# PCF8574.net
KiCad netlist of a schematic drawn in EAGLE
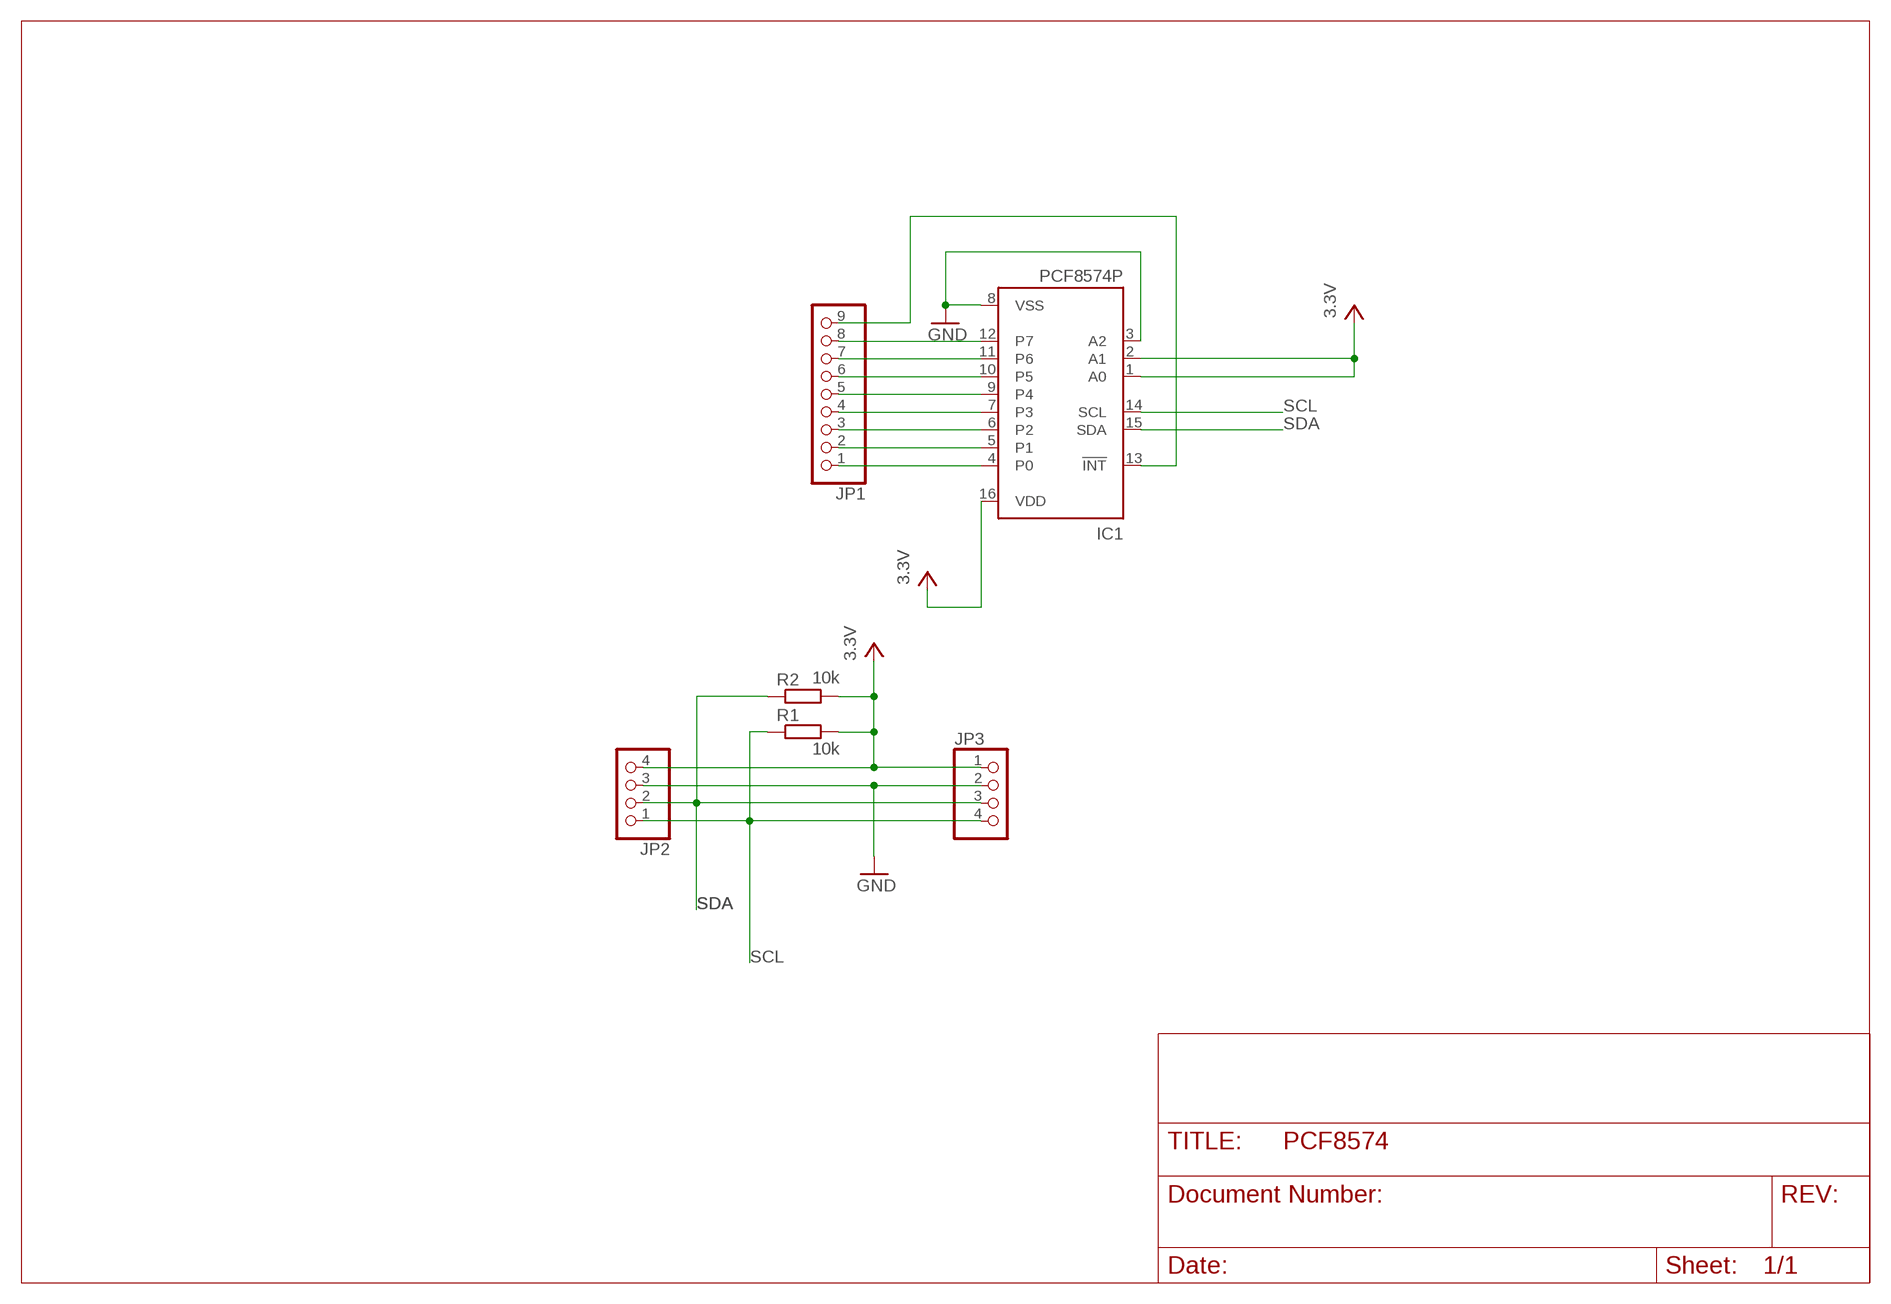
[diagram p0: schematic, sheet 1]

(export (version "E")
  (design (tool "Eeschema 10.0.6"))
  (components
    (comp (ref "IC1")
      (value "PCF8574P")
      (footprint "eagle-import:DIL16")
      (fields (field (name "MPN") "PCF8574PN"))
      (libsource (lib "eagle-import") (part "PCF8574P"))
    )
    (comp (ref "JP1")
      (value "PINHD-1X9")
      (footprint "eagle-import:1X09")
      (libsource (lib "eagle-import") (part "PINHD-1X9"))
    )
    (comp (ref "JP2")
      (value "PINHD-1X4/90")
      (footprint "eagle-import:1X04_90")
      (libsource (lib "eagle-import") (part "PINHD-1X4/90"))
    )
    (comp (ref "JP3")
      (value "PINHD-1X4/90")
      (footprint "eagle-import:1X04_90")
      (libsource (lib "eagle-import") (part "PINHD-1X4/90"))
    )
    (comp (ref "R1")
      (value "10k")
      (footprint "eagle-import:0309_12")
      (libsource (lib "eagle-import") (part "R-EU_0309/12"))
    )
    (comp (ref "R2")
      (value "10k")
      (footprint "eagle-import:0309_12")
      (libsource (lib "eagle-import") (part "R-EU_0309/12"))
    )
  )
  (nets
    (net (code "1") (name "/SCL") (class "Default")
      (node (ref "IC1") (pin "14") (pinfunction "SCL_14") (pintype "input"))
      (node (ref "JP2") (pin "1") (pinfunction "1_1") (pintype "passive"))
      (node (ref "JP3") (pin "4") (pinfunction "4_4") (pintype "passive"))
      (node (ref "R1") (pin "1") (pinfunction "1_1") (pintype "passive"))
    )
    (net (code "2") (name "/SDA") (class "Default")
      (node (ref "IC1") (pin "15") (pinfunction "SDA_15") (pintype "bidirectional"))
      (node (ref "JP2") (pin "2") (pinfunction "2_2") (pintype "passive"))
      (node (ref "JP3") (pin "3") (pinfunction "3_3") (pintype "passive"))
      (node (ref "R2") (pin "1") (pinfunction "1_1") (pintype "passive"))
    )
    (net (code "3") (name "3.3V") (class "Default")
      (node (ref "IC1") (pin "1") (pinfunction "A0_1") (pintype "input"))
      (node (ref "IC1") (pin "16") (pinfunction "VDD_16") (pintype "power_in"))
      (node (ref "IC1") (pin "2") (pinfunction "A1_2") (pintype "input"))
      (node (ref "JP2") (pin "4") (pinfunction "4_4") (pintype "passive"))
      (node (ref "JP3") (pin "1") (pinfunction "1_1") (pintype "passive"))
      (node (ref "R1") (pin "2") (pinfunction "2_2") (pintype "passive"))
      (node (ref "R2") (pin "2") (pinfunction "2_2") (pintype "passive"))
    )
    (net (code "4") (name "GND") (class "Default")
      (node (ref "IC1") (pin "3") (pinfunction "A2_3") (pintype "input"))
      (node (ref "IC1") (pin "8") (pinfunction "VSS_8") (pintype "power_in"))
      (node (ref "JP2") (pin "3") (pinfunction "3_3") (pintype "passive"))
      (node (ref "JP3") (pin "2") (pinfunction "2_2") (pintype "passive"))
    )
    (net (code "5") (name "Net-(IC1-P0)") (class "Default")
      (node (ref "IC1") (pin "4") (pinfunction "P0_4") (pintype "bidirectional"))
      (node (ref "JP1") (pin "1") (pinfunction "1_1") (pintype "passive"))
    )
    (net (code "6") (name "Net-(IC1-P1)") (class "Default")
      (node (ref "IC1") (pin "5") (pinfunction "P1_5") (pintype "bidirectional"))
      (node (ref "JP1") (pin "2") (pinfunction "2_2") (pintype "passive"))
    )
    (net (code "7") (name "Net-(IC1-P2)") (class "Default")
      (node (ref "IC1") (pin "6") (pinfunction "P2_6") (pintype "bidirectional"))
      (node (ref "JP1") (pin "3") (pinfunction "3_3") (pintype "passive"))
    )
    (net (code "8") (name "Net-(IC1-P3)") (class "Default")
      (node (ref "IC1") (pin "7") (pinfunction "P3_7") (pintype "bidirectional"))
      (node (ref "JP1") (pin "4") (pinfunction "4_4") (pintype "passive"))
    )
    (net (code "9") (name "Net-(IC1-P4)") (class "Default")
      (node (ref "IC1") (pin "9") (pinfunction "P4_9") (pintype "bidirectional"))
      (node (ref "JP1") (pin "5") (pinfunction "5_5") (pintype "passive"))
    )
    (net (code "10") (name "Net-(IC1-P5)") (class "Default")
      (node (ref "IC1") (pin "10") (pinfunction "P5_10") (pintype "bidirectional"))
      (node (ref "JP1") (pin "6") (pinfunction "6_6") (pintype "passive"))
    )
    (net (code "11") (name "Net-(IC1-P6)") (class "Default")
      (node (ref "IC1") (pin "11") (pinfunction "P6_11") (pintype "bidirectional"))
      (node (ref "JP1") (pin "7") (pinfunction "7_7") (pintype "passive"))
    )
    (net (code "12") (name "Net-(IC1-P7)") (class "Default")
      (node (ref "IC1") (pin "12") (pinfunction "P7_12") (pintype "bidirectional"))
      (node (ref "JP1") (pin "8") (pinfunction "8_8") (pintype "passive"))
    )
    (net (code "13") (name "Net-(IC1-~{INT})") (class "Default")
      (node (ref "IC1") (pin "13") (pinfunction "~{INT}_13") (pintype "output"))
      (node (ref "JP1") (pin "9") (pinfunction "9_9") (pintype "passive"))
    )
  )
)
